# design.net
KiCad netlist of a schematic drawn in Altium Designer
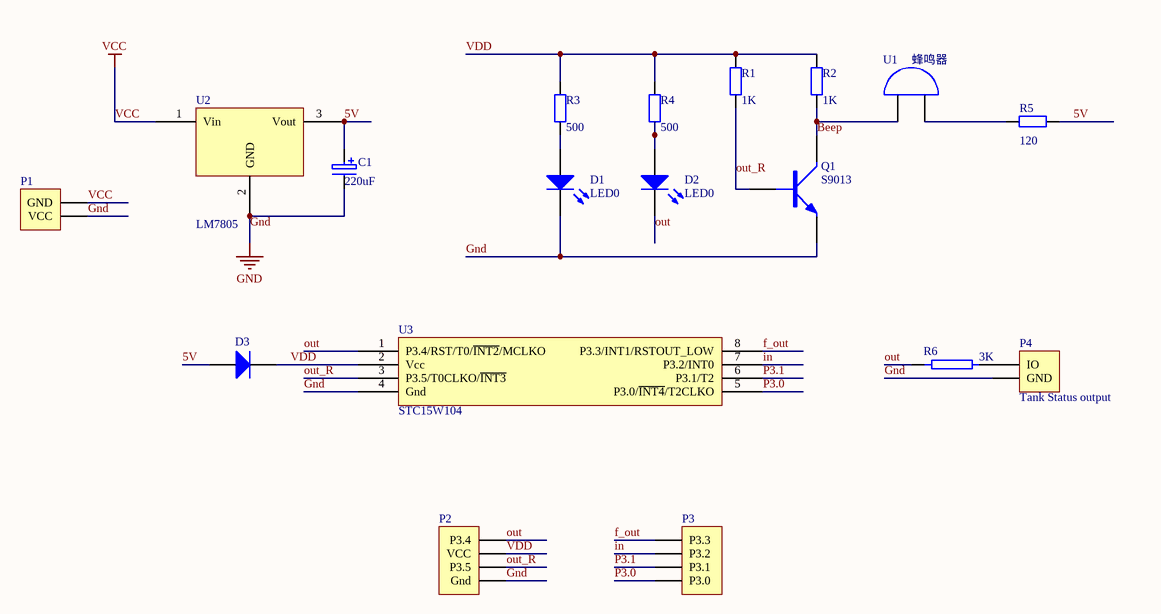
[diagram p0: 主板.SchDoc]

(export (version "E")
  (design (tool "Eeschema 10.0.6"))
  (components
    (comp (ref "C1")
      (value "220uF")
      (footprint "RB1")
      (fields (field (name "Comment") "CAP3"))
      (libsource (lib "C电容") (part "CAP3"))
    )
    (comp (ref "D1")
      (value "LED0")
      (footprint "LED-0")
      (description "Typical INFRARED GaAs LED")
      (fields (field (name "PUBLISHER") "Altium Limited"))
      (libsource (lib "Miscellaneous Devices") (part "LED0"))
    )
    (comp (ref "D2")
      (value "LED0")
      (footprint "LED-0")
      (description "Typical INFRARED GaAs LED")
      (fields (field (name "PUBLISHER") "Altium Limited"))
      (libsource (lib "Miscellaneous Devices") (part "LED0"))
    )
    (comp (ref "D3")
      (value "1N4007")
      (footprint "DO-41")
      (description "1 Amp General Purpose Rectifier")
      (fields (field (name "PUBLISHER") "Altium Limited"))
      (libsource (lib "Miscellaneous Devices") (part "Diode 1N4007"))
    )
    (comp (ref "P1")
      (value "Header 2")
      (footprint "HDR1X2")
      (description "Header, 2-Pin")
      (fields (field (name "PUBLISHER") "Altium Limited"))
      (libsource (lib "") (part "Header 2_1"))
    )
    (comp (ref "P2")
      (value "Header 4")
      (footprint "HDR1X4")
      (description "Header, 4-Pin")
      (fields (field (name "PUBLISHER") "Altium Limited"))
      (libsource (lib "") (part "Header 4_1"))
    )
    (comp (ref "P3")
      (value "Header 4")
      (footprint "HDR1X4")
      (description "Header, 4-Pin")
      (fields (field (name "PUBLISHER") "Altium Limited"))
      (libsource (lib "Miscellaneous Connectors") (part "Header 4"))
    )
    (comp (ref "P4")
      (value "Tank Status output")
      (footprint "HDR1X2")
      (description "Header, 2-Pin")
      (fields (field (name "PUBLISHER") "Altium Limited"))
      (libsource (lib "Miscellaneous Connectors") (part "Header 2"))
    )
    (comp (ref "Q1")
      (value "S9013")
      (footprint "TO92A")
      (description "?")
      (libsource (lib "V三极管") (part "NPN1E2B3C"))
    )
    (comp (ref "R1")
      (value "1K")
      (footprint "AXIAL-0.4")
      (description "Resistor")
      (fields (field (name "Comment") "Res2") (field (name "PUBLISHER") "Altium Limited"))
      (libsource (lib "") (part "Res2_1"))
    )
    (comp (ref "R2")
      (value "1K")
      (footprint "AXIAL-0.4")
      (description "Resistor")
      (fields (field (name "Comment") "Res2") (field (name "PUBLISHER") "Altium Limited"))
      (libsource (lib "") (part "Res2_1"))
    )
    (comp (ref "R3")
      (value "500")
      (footprint "AXIAL-0.4")
      (description "Resistor")
      (fields (field (name "Comment") "Res2") (field (name "PUBLISHER") "Altium Limited"))
      (libsource (lib "") (part "Res2_1"))
    )
    (comp (ref "R4")
      (value "500")
      (footprint "AXIAL-0.4")
      (description "Resistor")
      (fields (field (name "Comment") "Res2") (field (name "PUBLISHER") "Altium Limited"))
      (libsource (lib "") (part "Res2_1"))
    )
    (comp (ref "R5")
      (value "120")
      (footprint "AXIAL-0.4")
      (description "Resistor")
      (fields (field (name "Comment") "Res2") (field (name "PUBLISHER") "Altium Limited"))
      (libsource (lib "Miscellaneous Devices") (part "Res2"))
    )
    (comp (ref "R6") (value "3K") (footprint "AXIAL0.4") (libsource (lib "电阻") (part "RES")))
    (comp (ref "U1") (value "蜂鸣器") (description "Bell") (libsource (lib "声亮元件") (part "蜂鸣器")))
    (comp (ref "U2") (value "LM7805") (footprint "TO257V") (libsource (lib "稳压管") (part "78**")))
    (comp (ref "U3")
      (value "STC15W104")
      (footprint "DFN8")
      (libsource (lib "stcmcu_altium_lib") (part "STC15W10x_DIP8_SOP8_DFN8"))
    )
  )
  (nets
    (net (code "1") (name "/5V") (class "Default")
      (node (ref "C1") (pin "1") (pintype "passive"))
      (node (ref "D3") (pin "1") (pinfunction "A_1") (pintype "passive"))
      (node (ref "R5") (pin "2") (pinfunction "2_2") (pintype "passive"))
      (node (ref "U2") (pin "3") (pinfunction "Vout_3") (pintype "passive"))
    )
    (net (code "2") (name "/Beep") (class "Default")
      (node (ref "Q1") (pin "3") (pinfunction "C_3") (pintype "passive"))
      (node (ref "R2") (pin "1") (pinfunction "1_1") (pintype "passive"))
      (node (ref "U1") (pin "1") (pinfunction "A_1") (pintype "passive"))
    )
    (net (code "3") (name "/P3.0") (class "Default")
      (node (ref "P3") (pin "4") (pinfunction "P3.0_4") (pintype "passive"))
      (node (ref "U3") (pin "5") (pinfunction "P3.0/~{INT4}/T2CLKO_5") (pintype "passive"))
    )
    (net (code "4") (name "/P3.1") (class "Default")
      (node (ref "P3") (pin "3") (pinfunction "P3.1_3") (pintype "passive"))
      (node (ref "U3") (pin "6") (pinfunction "P3.1/T2_6") (pintype "passive"))
    )
    (net (code "5") (name "/VDD") (class "Default")
      (node (ref "D3") (pin "2") (pinfunction "K_2") (pintype "passive"))
      (node (ref "P2") (pin "2") (pinfunction "VCC_2") (pintype "passive"))
      (node (ref "R1") (pin "2") (pinfunction "2_2") (pintype "passive"))
      (node (ref "R2") (pin "2") (pinfunction "2_2") (pintype "passive"))
      (node (ref "R3") (pin "2") (pinfunction "2_2") (pintype "passive"))
      (node (ref "R4") (pin "2") (pinfunction "2_2") (pintype "passive"))
      (node (ref "U3") (pin "2") (pinfunction "Vcc_2") (pintype "passive"))
    )
    (net (code "6") (name "/f_out") (class "Default")
      (node (ref "P3") (pin "1") (pinfunction "P3.3_1") (pintype "passive"))
      (node (ref "U3") (pin "8") (pinfunction "P3.3/INT1/RSTOUT_LOW_8") (pintype "passive"))
    )
    (net (code "7") (name "/in") (class "Default")
      (node (ref "P3") (pin "2") (pinfunction "P3.2_2") (pintype "passive"))
      (node (ref "U3") (pin "7") (pinfunction "P3.2/INT0_7") (pintype "passive"))
    )
    (net (code "8") (name "/out") (class "Default")
      (node (ref "D2") (pin "2") (pinfunction "K_2") (pintype "passive"))
      (node (ref "P2") (pin "1") (pinfunction "P3.4_1") (pintype "passive"))
      (node (ref "R6") (pin "1") (pinfunction "1_1") (pintype "passive"))
      (node (ref "U3") (pin "1") (pinfunction "P3.4/RST/T0/~{INT2}/MCLKO_1") (pintype "passive"))
    )
    (net (code "9") (name "/out_R") (class "Default")
      (node (ref "P2") (pin "3") (pinfunction "P3.5_3") (pintype "passive"))
      (node (ref "Q1") (pin "2") (pinfunction "B_2") (pintype "passive"))
      (node (ref "R1") (pin "1") (pinfunction "1_1") (pintype "passive"))
      (node (ref "U3") (pin "3") (pinfunction "P3.5/T0CLKO/~{INT3}_3") (pintype "passive"))
    )
    (net (code "10") (name "GND") (class "Default")
      (node (ref "C1") (pin "2") (pintype "passive"))
      (node (ref "D1") (pin "2") (pinfunction "K_2") (pintype "passive"))
      (node (ref "P1") (pin "1") (pinfunction "VCC_1") (pintype "passive"))
      (node (ref "P2") (pin "4") (pinfunction "Gnd_4") (pintype "passive"))
      (node (ref "P4") (pin "2") (pinfunction "GND_2") (pintype "passive"))
      (node (ref "Q1") (pin "1") (pinfunction "E_1") (pintype "passive"))
      (node (ref "U2") (pin "2") (pinfunction "GND_2") (pintype "passive"))
      (node (ref "U3") (pin "4") (pinfunction "Gnd_4") (pintype "passive"))
    )
    (net (code "11") (name "Net-(D1-A)") (class "Default")
      (node (ref "D1") (pin "1") (pinfunction "A_1") (pintype "passive"))
      (node (ref "R3") (pin "1") (pinfunction "1_1") (pintype "passive"))
    )
    (net (code "12") (name "Net-(D2-A)") (class "Default")
      (node (ref "D2") (pin "1") (pinfunction "A_1") (pintype "passive"))
      (node (ref "R4") (pin "1") (pinfunction "1_1") (pintype "passive"))
    )
    (net (code "13") (name "Net-(P4-IO)") (class "Default")
      (node (ref "P4") (pin "1") (pinfunction "IO_1") (pintype "passive"))
      (node (ref "R6") (pin "2") (pinfunction "2_2") (pintype "passive"))
    )
    (net (code "14") (name "Net-(U1-B)") (class "Default")
      (node (ref "R5") (pin "1") (pinfunction "1_1") (pintype "passive"))
      (node (ref "U1") (pin "2") (pinfunction "B_2") (pintype "passive"))
    )
    (net (code "15") (name "VCC") (class "Default")
      (node (ref "P1") (pin "2") (pinfunction "GND_2") (pintype "passive"))
      (node (ref "U2") (pin "1") (pinfunction "Vin_1") (pintype "passive"))
    )
  )
)
